# 1_Power.net
KiCad netlist of a schematic drawn in Altium Designer
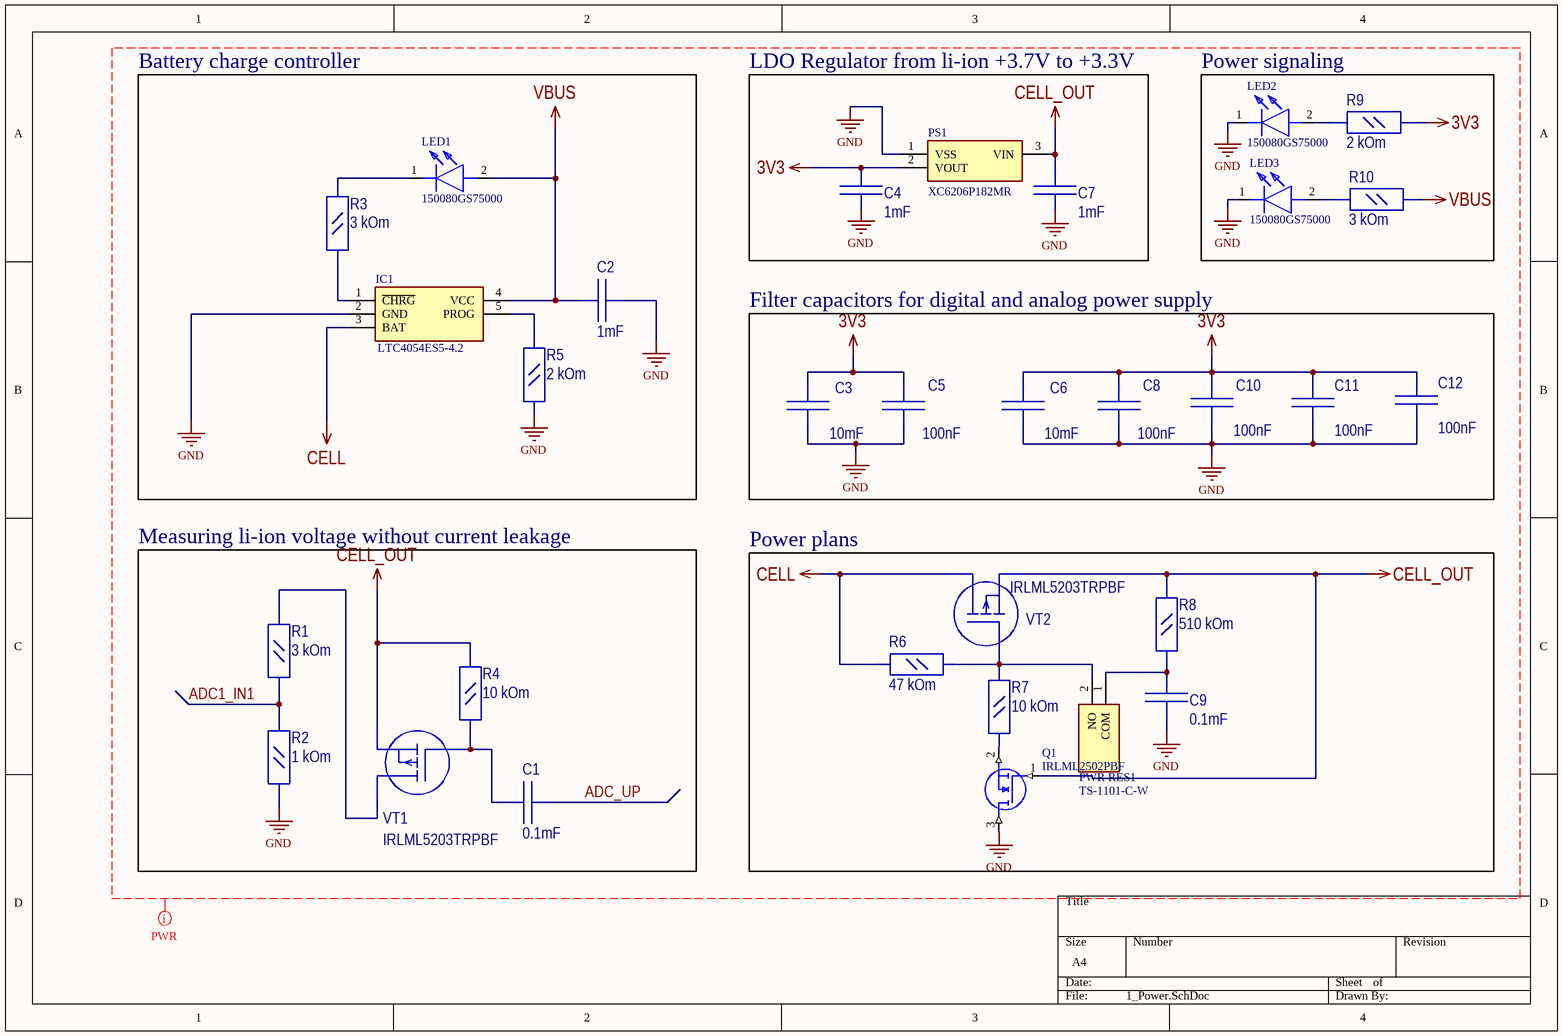
[diagram p0: 1_Power.SchDoc]

(export (version "E")
  (design (tool "Eeschema 10.0.6"))
  (components
    (comp (ref "C1") (value "0.1mF") (footprint "C_0805") (libsource (lib "2.Capasitors") (part "C_0805")))
    (comp (ref "C2") (value "1mF") (footprint "C_0805") (libsource (lib "2.Capasitors") (part "C_0805")))
    (comp (ref "C3") (value "10mF") (footprint "C_0805") (libsource (lib "2.Capasitors") (part "C_0805")))
    (comp (ref "C4") (value "1mF") (footprint "C_0805") (libsource (lib "2.Capasitors") (part "C_0805")))
    (comp (ref "C5") (value "100nF") (footprint "C_0805") (libsource (lib "2.Capasitors") (part "C_0805")))
    (comp (ref "C6") (value "10mF") (footprint "C_0805") (libsource (lib "2.Capasitors") (part "C_0805")))
    (comp (ref "C7") (value "1mF") (footprint "C_0805") (libsource (lib "2.Capasitors") (part "C_0805")))
    (comp (ref "C8") (value "100nF") (footprint "C_0805") (libsource (lib "2.Capasitors") (part "C_0805")))
    (comp (ref "C9") (value "0.1mF") (footprint "C_0805") (libsource (lib "2.Capasitors") (part "C_0805")))
    (comp (ref "C10") (value "100nF") (footprint "C_0805") (libsource (lib "2.Capasitors") (part "C_0805")))
    (comp (ref "C11") (value "100nF") (footprint "C_0805") (libsource (lib "2.Capasitors") (part "C_0805")))
    (comp (ref "C12") (value "100nF") (footprint "C_0805") (libsource (lib "2.Capasitors") (part "C_0805")))
    (comp (ref "IC1")
      (value "LTC4054ES5-4.2")
      (footprint "SamacSys:SOT95P280X100-5N")
      (description "Integrated Circuit")
      (fields (field (name "MOUSER PART NUMBER") "584-LTC4054ES5-4.2"))
      (libsource (lib "*") (part "LTC4054ES5-4.2"))
    )
    (comp (ref "LED1")
      (value "150080GS75000")
      (footprint "SamacSys:LEDM2012X80N")
      (description "LED")
      (fields (field (name "MOUSER PART NUMBER") "710-150080GS75000"))
      (libsource (lib "*") (part "150080GS75000"))
    )
    (comp (ref "LED2")
      (value "150080GS75000")
      (footprint "SamacSys:LEDM2012X80N")
      (description "LED")
      (fields (field (name "MOUSER PART NUMBER") "710-150080GS75000"))
      (libsource (lib "*") (part "150080GS75000"))
    )
    (comp (ref "LED3")
      (value "150080GS75000")
      (footprint "SamacSys:LEDM2012X80N")
      (description "LED")
      (fields (field (name "MOUSER PART NUMBER") "710-150080GS75000"))
      (libsource (lib "*") (part "150080GS75000"))
    )
    (comp (ref "PS1")
      (value "XC6206P182MR")
      (footprint "SamacSys:SOT95P280X130-3N")
      (description "Power Supply")
      (libsource (lib "*") (part "XC6206P182MR"))
    )
    (comp (ref "PWR RES1")
      (value "TS-1101-C-W")
      (footprint "SamacSys:TS1101CW")
      (description "Switch")
      (libsource (lib "*") (part "TS-1101-C-W"))
    )
    (comp (ref "Q1")
      (value "IRLML2502PBF")
      (footprint "SamacSys:SOT95P237X112-3N")
      (description "MOSFET (N-Channel)")
      (libsource (lib "*") (part "IRLML2502PBF"))
    )
    (comp (ref "R1") (value "3 kOm") (footprint "R_0805") (libsource (lib "1.Resistors") (part "R_0805")))
    (comp (ref "R2") (value "1 kOm") (footprint "R_0805") (libsource (lib "1.Resistors") (part "R_0805")))
    (comp (ref "R3") (value "3 kOm") (footprint "R_0805") (libsource (lib "1.Resistors") (part "R_0805")))
    (comp (ref "R4") (value "10 kOm") (footprint "R_0805") (libsource (lib "1.Resistors") (part "R_0805")))
    (comp (ref "R5") (value "2 kOm") (footprint "R_0805") (libsource (lib "1.Resistors") (part "R_0805")))
    (comp (ref "R6") (value "47 kOm") (footprint "R_0805") (libsource (lib "1.Resistors") (part "R_0805")))
    (comp (ref "R7") (value "10 kOm") (footprint "R_0805") (libsource (lib "1.Resistors") (part "R_0805")))
    (comp (ref "R8") (value "510 kOm") (footprint "R_0805") (libsource (lib "1.Resistors") (part "R_0805")))
    (comp (ref "R9") (value "2 kOm") (footprint "R_0805") (libsource (lib "") (part "R_0805_1")))
    (comp (ref "R10") (value "3 kOm") (footprint "R_0805") (libsource (lib "1.Resistors") (part "R_0805")))
    (comp (ref "VT1")
      (value "IRLML5203TRPBF")
      (footprint "SOT23")
      (description "Транзистор, P-канал 30В 3A logic")
      (libsource (lib "5.Transistors") (part "IRLML5203TRPBF"))
    )
    (comp (ref "VT2")
      (value "IRLML5203TRPBF")
      (footprint "SOT23")
      (description "Транзистор, P-канал 30В 3A logic")
      (libsource (lib "5.Transistors") (part "IRLML5203TRPBF"))
    )
  )
  (nets
    (net (code "1") (name "/ADC1_IN1") (class "Default")
      (node (ref "R1") (pin "1") (pinfunction "1_1") (pintype "passive"))
      (node (ref "R2") (pin "2") (pinfunction "2_2") (pintype "passive"))
    )
    (net (code "2") (name "/ADC_UP") (class "Default")
      (node (ref "C1") (pin "1") (pinfunction "1_1") (pintype "passive"))
    )
    (net (code "3") (name "3V3") (class "Default")
      (node (ref "C10") (pin "2") (pinfunction "2_2") (pintype "passive"))
      (node (ref "C11") (pin "2") (pinfunction "2_2") (pintype "passive"))
      (node (ref "C12") (pin "2") (pinfunction "2_2") (pintype "passive"))
      (node (ref "C3") (pin "2") (pinfunction "2_2") (pintype "passive"))
      (node (ref "C4") (pin "2") (pinfunction "2_2") (pintype "passive"))
      (node (ref "C5") (pin "2") (pinfunction "2_2") (pintype "passive"))
      (node (ref "C6") (pin "2") (pinfunction "2_2") (pintype "passive"))
      (node (ref "C8") (pin "2") (pinfunction "2_2") (pintype "passive"))
      (node (ref "PS1") (pin "2") (pinfunction "VOUT_2") (pintype "passive"))
      (node (ref "R9") (pin "1") (pinfunction "1_1") (pintype "passive"))
    )
    (net (code "4") (name "CELL") (class "Default")
      (node (ref "IC1") (pin "3") (pinfunction "BAT_3") (pintype "passive"))
      (node (ref "R6") (pin "2") (pinfunction "2_2") (pintype "passive"))
      (node (ref "VT2") (pin "3") (pinfunction "D_3") (pintype "passive"))
    )
    (net (code "5") (name "CELL_OUT") (class "Default")
      (node (ref "C7") (pin "2") (pinfunction "2_2") (pintype "passive"))
      (node (ref "PS1") (pin "3") (pinfunction "VIN_3") (pintype "passive"))
      (node (ref "Q1") (pin "1") (pinfunction "G_1") (pintype "input"))
      (node (ref "R4") (pin "2") (pinfunction "2_2") (pintype "passive"))
      (node (ref "R8") (pin "2") (pinfunction "2_2") (pintype "passive"))
      (node (ref "VT1") (pin "2") (pinfunction "S_2") (pintype "passive"))
      (node (ref "VT2") (pin "2") (pinfunction "S_2") (pintype "passive"))
    )
    (net (code "6") (name "GND") (class "Default")
      (node (ref "C10") (pin "1") (pinfunction "1_1") (pintype "passive"))
      (node (ref "C11") (pin "1") (pinfunction "1_1") (pintype "passive"))
      (node (ref "C12") (pin "1") (pinfunction "1_1") (pintype "passive"))
      (node (ref "C2") (pin "2") (pinfunction "2_2") (pintype "passive"))
      (node (ref "C3") (pin "1") (pinfunction "1_1") (pintype "passive"))
      (node (ref "C4") (pin "1") (pinfunction "1_1") (pintype "passive"))
      (node (ref "C5") (pin "1") (pinfunction "1_1") (pintype "passive"))
      (node (ref "C6") (pin "1") (pinfunction "1_1") (pintype "passive"))
      (node (ref "C7") (pin "1") (pinfunction "1_1") (pintype "passive"))
      (node (ref "C8") (pin "1") (pinfunction "1_1") (pintype "passive"))
      (node (ref "C9") (pin "1") (pinfunction "1_1") (pintype "passive"))
      (node (ref "IC1") (pin "2") (pinfunction "GND_2") (pintype "passive"))
      (node (ref "LED2") (pin "1") (pinfunction "K_1") (pintype "passive"))
      (node (ref "LED3") (pin "1") (pinfunction "K_1") (pintype "passive"))
      (node (ref "PS1") (pin "1") (pinfunction "VSS_1") (pintype "passive"))
      (node (ref "Q1") (pin "3") (pinfunction "D_3") (pintype "input"))
      (node (ref "R2") (pin "1") (pinfunction "1_1") (pintype "passive"))
      (node (ref "R5") (pin "1") (pinfunction "1_1") (pintype "passive"))
    )
    (net (code "7") (name "Net-(IC1-PROG)") (class "Default")
      (node (ref "IC1") (pin "5") (pinfunction "PROG_5") (pintype "passive"))
      (node (ref "R5") (pin "2") (pinfunction "2_2") (pintype "passive"))
    )
    (net (code "8") (name "Net-(IC1-~{CHRG})") (class "Default")
      (node (ref "IC1") (pin "1") (pinfunction "~{CHRG}_1") (pintype "passive"))
      (node (ref "R3") (pin "1") (pinfunction "1_1") (pintype "passive"))
    )
    (net (code "9") (name "Net-(LED1-K)") (class "Default")
      (node (ref "LED1") (pin "1") (pinfunction "K_1") (pintype "passive"))
      (node (ref "R3") (pin "2") (pinfunction "2_2") (pintype "passive"))
    )
    (net (code "10") (name "Net-(LED2-A)") (class "Default")
      (node (ref "LED2") (pin "2") (pinfunction "A_2") (pintype "passive"))
      (node (ref "R9") (pin "2") (pinfunction "2_2") (pintype "passive"))
    )
    (net (code "11") (name "Net-(LED3-A)") (class "Default")
      (node (ref "LED3") (pin "2") (pinfunction "A_2") (pintype "passive"))
      (node (ref "R10") (pin "2") (pinfunction "2_2") (pintype "passive"))
    )
    (net (code "12") (name "Net-(PWR RES1-COM)") (class "Default")
      (node (ref "C9") (pin "2") (pinfunction "2_2") (pintype "passive"))
      (node (ref "PWR RES1") (pin "1") (pinfunction "COM_1") (pintype "passive"))
      (node (ref "R8") (pin "1") (pinfunction "1_1") (pintype "passive"))
    )
    (net (code "13") (name "Net-(PWR RES1-NO)") (class "Default")
      (node (ref "PWR RES1") (pin "2") (pinfunction "NO_2") (pintype "passive"))
      (node (ref "R6") (pin "1") (pinfunction "1_1") (pintype "passive"))
      (node (ref "R7") (pin "2") (pinfunction "2_2") (pintype "passive"))
      (node (ref "VT2") (pin "1") (pinfunction "G_1") (pintype "passive"))
    )
    (net (code "14") (name "Net-(Q1-S)") (class "Default")
      (node (ref "Q1") (pin "2") (pinfunction "S_2") (pintype "output"))
      (node (ref "R7") (pin "1") (pinfunction "1_1") (pintype "passive"))
    )
    (net (code "15") (name "Net-(VT1-D)") (class "Default")
      (node (ref "R1") (pin "2") (pinfunction "2_2") (pintype "passive"))
      (node (ref "VT1") (pin "3") (pinfunction "D_3") (pintype "passive"))
    )
    (net (code "16") (name "Net-(VT1-G)") (class "Default")
      (node (ref "C1") (pin "2") (pinfunction "2_2") (pintype "passive"))
      (node (ref "R4") (pin "1") (pinfunction "1_1") (pintype "passive"))
      (node (ref "VT1") (pin "1") (pinfunction "G_1") (pintype "passive"))
    )
    (net (code "17") (name "VBUS") (class "Default")
      (node (ref "C2") (pin "1") (pinfunction "1_1") (pintype "passive"))
      (node (ref "IC1") (pin "4") (pinfunction "VCC_4") (pintype "passive"))
      (node (ref "LED1") (pin "2") (pinfunction "A_2") (pintype "passive"))
      (node (ref "R10") (pin "1") (pinfunction "1_1") (pintype "passive"))
    )
  )
)
